# Adapter_XDS_110.net
KiCad netlist of a schematic drawn in Altium Designer
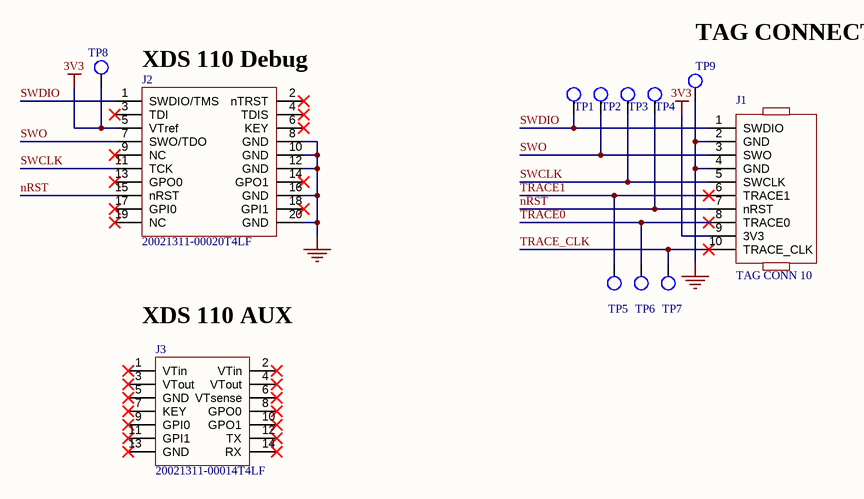
[diagram p0: Adapter_XDS_110.SchDoc]

(export (version "E")
  (design (tool "Eeschema 10.0.6"))
  (components
    (comp (ref "J1")
      (value "TAG CONN 10")
      (footprint "CONN HDR RECPT 20 2.54 TH TAG CONNECT 10")
      (description "Conn Shrouded Header HDR 10 POS 2.54mm Solder ST Thru-Hole")
      (fields
        (field (name "MANUFACTURER") "On-Shore Technology")
        (field (name "MANUFACTURER PART NUMBER") "302-S101")
      )
      (libsource (lib "Adapter_SchematicLib") (part "CONN HDR RECPT 10 2.54mm TH SWV"))
    )
    (comp (ref "J2")
      (value "20021311-00020T4LF")
      (footprint "CONN HDR PLUG 20 1.27 TH XDS110 DEBUG")
      (description "Dual Row 20 Position 1.27 mm Board to Board Through Hole Female Socket Connector")
      (libsource (lib "Adapter_SchematicLib") (part "CONN HDR RECPT 20 1.27mm TH 20021311-00020T4LF"))
    )
    (comp (ref "J3")
      (value "20021311-00014T4LF")
      (footprint "CONN HDR PLUG 14 1.27 TH XDS110 AUX")
      (description "1.27mm (0.05in.) pitch, Receptacle Top entry, 14 contacts")
      (libsource (lib "Adapter_SchematicLib") (part "CONN HDR RECPT 14 1.27mm TH 20021311-00014T4LF"))
    )
    (comp (ref "TP1")
      (value "1mm")
      (footprint "TESTPOINT_SMT")
      (description "SMT testpoint")
      (libsource (lib "Adapter_SchematicLib") (part "TP 1mm"))
    )
    (comp (ref "TP2")
      (value "1mm")
      (footprint "TESTPOINT_SMT")
      (description "SMT testpoint")
      (libsource (lib "Adapter_SchematicLib") (part "TP 1mm"))
    )
    (comp (ref "TP3")
      (value "1mm")
      (footprint "TESTPOINT_SMT")
      (description "SMT testpoint")
      (libsource (lib "Adapter_SchematicLib") (part "TP 1mm"))
    )
    (comp (ref "TP4")
      (value "1mm")
      (footprint "TESTPOINT_SMT")
      (description "SMT testpoint")
      (libsource (lib "Adapter_SchematicLib") (part "TP 1mm"))
    )
    (comp (ref "TP5")
      (value "1mm")
      (footprint "TESTPOINT_SMT")
      (description "SMT testpoint")
      (libsource (lib "Adapter_SchematicLib") (part "TP 1mm"))
    )
    (comp (ref "TP6")
      (value "1mm")
      (footprint "TESTPOINT_SMT")
      (description "SMT testpoint")
      (libsource (lib "Adapter_SchematicLib") (part "TP 1mm"))
    )
    (comp (ref "TP7")
      (value "1mm")
      (footprint "TESTPOINT_SMT")
      (description "SMT testpoint")
      (libsource (lib "Adapter_SchematicLib") (part "TP 1mm"))
    )
    (comp (ref "TP8")
      (value "1mm")
      (footprint "TESTPOINT_SMT")
      (description "SMT testpoint")
      (libsource (lib "Adapter_SchematicLib") (part "TP 1mm"))
    )
    (comp (ref "TP9")
      (value "1mm")
      (footprint "TESTPOINT_SMT")
      (description "SMT testpoint")
      (libsource (lib "Adapter_SchematicLib") (part "TP 1mm"))
    )
  )
  (nets
    (net (code "1") (name "/SWCLK") (class "Default")
      (node (ref "J1") (pin "5") (pinfunction "SWCLK_5") (pintype "passive"))
      (node (ref "J2") (pin "11") (pinfunction "TCK_11") (pintype "passive"))
      (node (ref "TP3") (pin "1") (pinfunction "1_1") (pintype "passive"))
    )
    (net (code "2") (name "/SWDIO") (class "Default")
      (node (ref "J1") (pin "1") (pinfunction "SWDIO_1") (pintype "passive"))
      (node (ref "J2") (pin "1") (pinfunction "SWDIO/TMS_1") (pintype "passive"))
      (node (ref "TP1") (pin "1") (pinfunction "1_1") (pintype "passive"))
    )
    (net (code "3") (name "/SWO") (class "Default")
      (node (ref "J1") (pin "3") (pinfunction "SWO_3") (pintype "passive"))
      (node (ref "J2") (pin "7") (pinfunction "SWO/TDO_7") (pintype "passive"))
      (node (ref "TP2") (pin "1") (pinfunction "1_1") (pintype "passive"))
    )
    (net (code "4") (name "/TRACE0") (class "Default")
      (node (ref "J1") (pin "8") (pinfunction "TRACE0_8") (pintype "passive"))
      (node (ref "TP6") (pin "1") (pinfunction "1_1") (pintype "passive"))
    )
    (net (code "5") (name "/TRACE1") (class "Default")
      (node (ref "J1") (pin "6") (pinfunction "TRACE1_6") (pintype "passive"))
      (node (ref "TP5") (pin "1") (pinfunction "1_1") (pintype "passive"))
    )
    (net (code "6") (name "/TRACE_CLK") (class "Default")
      (node (ref "J1") (pin "10") (pinfunction "TRACE_CLK_10") (pintype "passive"))
      (node (ref "TP7") (pin "1") (pinfunction "1_1") (pintype "passive"))
    )
    (net (code "7") (name "/nRST") (class "Default")
      (node (ref "J1") (pin "7") (pinfunction "nRST_7") (pintype "passive"))
      (node (ref "J2") (pin "15") (pinfunction "nRST_15") (pintype "passive"))
      (node (ref "TP4") (pin "1") (pinfunction "1_1") (pintype "passive"))
    )
    (net (code "8") (name "3V3") (class "Default")
      (node (ref "J1") (pin "9") (pinfunction "3V3_9") (pintype "passive"))
      (node (ref "J2") (pin "5") (pinfunction "VTref_5") (pintype "passive"))
      (node (ref "TP8") (pin "1") (pinfunction "1_1") (pintype "passive"))
    )
    (net (code "9") (name "GND") (class "Default")
      (node (ref "J1") (pin "2") (pinfunction "GND_2") (pintype "passive"))
      (node (ref "J1") (pin "4") (pinfunction "GND_4") (pintype "passive"))
      (node (ref "J2") (pin "10") (pinfunction "GND_10") (pintype "passive"))
      (node (ref "J2") (pin "12") (pinfunction "GND_12") (pintype "passive"))
      (node (ref "J2") (pin "16") (pinfunction "GND_16") (pintype "passive"))
      (node (ref "J2") (pin "20") (pinfunction "GND_20") (pintype "passive"))
      (node (ref "J2") (pin "8") (pinfunction "GND_8") (pintype "passive"))
      (node (ref "TP9") (pin "1") (pinfunction "1_1") (pintype "passive"))
    )
    (net (code "10") (name "unconnected-(J2-GPI0-Pad17)") (class "Default")
      (node (ref "J2") (pin "17") (pinfunction "GPI0_17") (pintype "passive+no_connect"))
    )
    (net (code "11") (name "unconnected-(J2-GPI1-Pad18)") (class "Default")
      (node (ref "J2") (pin "18") (pinfunction "GPI1_18") (pintype "passive+no_connect"))
    )
    (net (code "12") (name "unconnected-(J2-GPO0-Pad13)") (class "Default")
      (node (ref "J2") (pin "13") (pinfunction "GPO0_13") (pintype "passive+no_connect"))
    )
    (net (code "13") (name "unconnected-(J2-GPO1-Pad14)") (class "Default")
      (node (ref "J2") (pin "14") (pinfunction "GPO1_14") (pintype "passive+no_connect"))
    )
    (net (code "14") (name "unconnected-(J2-KEY-Pad6)") (class "Default")
      (node (ref "J2") (pin "6") (pinfunction "KEY_6") (pintype "passive+no_connect"))
    )
    (net (code "15") (name "unconnected-(J2-NC-Pad9)") (class "Default")
      (node (ref "J2") (pin "9") (pinfunction "NC_9") (pintype "passive+no_connect"))
    )
    (net (code "16") (name "unconnected-(J2-NC-Pad19)") (class "Default")
      (node (ref "J2") (pin "19") (pinfunction "NC_19") (pintype "passive+no_connect"))
    )
    (net (code "17") (name "unconnected-(J2-TDI-Pad3)") (class "Default")
      (node (ref "J2") (pin "3") (pinfunction "TDI_3") (pintype "passive+no_connect"))
    )
    (net (code "18") (name "unconnected-(J2-TDIS-Pad4)") (class "Default")
      (node (ref "J2") (pin "4") (pinfunction "TDIS_4") (pintype "passive+no_connect"))
    )
    (net (code "19") (name "unconnected-(J2-nTRST-Pad2)") (class "Default")
      (node (ref "J2") (pin "2") (pinfunction "nTRST_2") (pintype "passive+no_connect"))
    )
    (net (code "20") (name "unconnected-(J3-GND-Pad5)") (class "Default")
      (node (ref "J3") (pin "5") (pinfunction "GND_5") (pintype "passive+no_connect"))
    )
    (net (code "21") (name "unconnected-(J3-GND-Pad13)") (class "Default")
      (node (ref "J3") (pin "13") (pinfunction "GND_13") (pintype "passive+no_connect"))
    )
    (net (code "22") (name "unconnected-(J3-GPI0-Pad9)") (class "Default")
      (node (ref "J3") (pin "9") (pinfunction "GPI0_9") (pintype "passive+no_connect"))
    )
    (net (code "23") (name "unconnected-(J3-GPI1-Pad11)") (class "Default")
      (node (ref "J3") (pin "11") (pinfunction "GPI1_11") (pintype "passive+no_connect"))
    )
    (net (code "24") (name "unconnected-(J3-GPO0-Pad8)") (class "Default")
      (node (ref "J3") (pin "8") (pinfunction "GPO0_8") (pintype "passive+no_connect"))
    )
    (net (code "25") (name "unconnected-(J3-GPO1-Pad10)") (class "Default")
      (node (ref "J3") (pin "10") (pinfunction "GPO1_10") (pintype "passive+no_connect"))
    )
    (net (code "26") (name "unconnected-(J3-KEY-Pad7)") (class "Default")
      (node (ref "J3") (pin "7") (pinfunction "KEY_7") (pintype "passive+no_connect"))
    )
    (net (code "27") (name "unconnected-(J3-RX-Pad14)") (class "Default")
      (node (ref "J3") (pin "14") (pinfunction "RX_14") (pintype "passive+no_connect"))
    )
    (net (code "28") (name "unconnected-(J3-TX-Pad12)") (class "Default")
      (node (ref "J3") (pin "12") (pinfunction "TX_12") (pintype "passive+no_connect"))
    )
    (net (code "29") (name "unconnected-(J3-VTin-Pad1)") (class "Default")
      (node (ref "J3") (pin "1") (pinfunction "VTin_1") (pintype "passive+no_connect"))
    )
    (net (code "30") (name "unconnected-(J3-VTin-Pad2)") (class "Default")
      (node (ref "J3") (pin "2") (pinfunction "VTin_2") (pintype "passive+no_connect"))
    )
    (net (code "31") (name "unconnected-(J3-VTout-Pad3)") (class "Default")
      (node (ref "J3") (pin "3") (pinfunction "VTout_3") (pintype "passive+no_connect"))
    )
    (net (code "32") (name "unconnected-(J3-VTout-Pad4)") (class "Default")
      (node (ref "J3") (pin "4") (pinfunction "VTout_4") (pintype "passive+no_connect"))
    )
    (net (code "33") (name "unconnected-(J3-VTsense-Pad6)") (class "Default")
      (node (ref "J3") (pin "6") (pinfunction "VTsense_6") (pintype "passive+no_connect"))
    )
  )
)
